# 18650_pack_v1.net
KiCad netlist of a schematic drawn in EAGLE
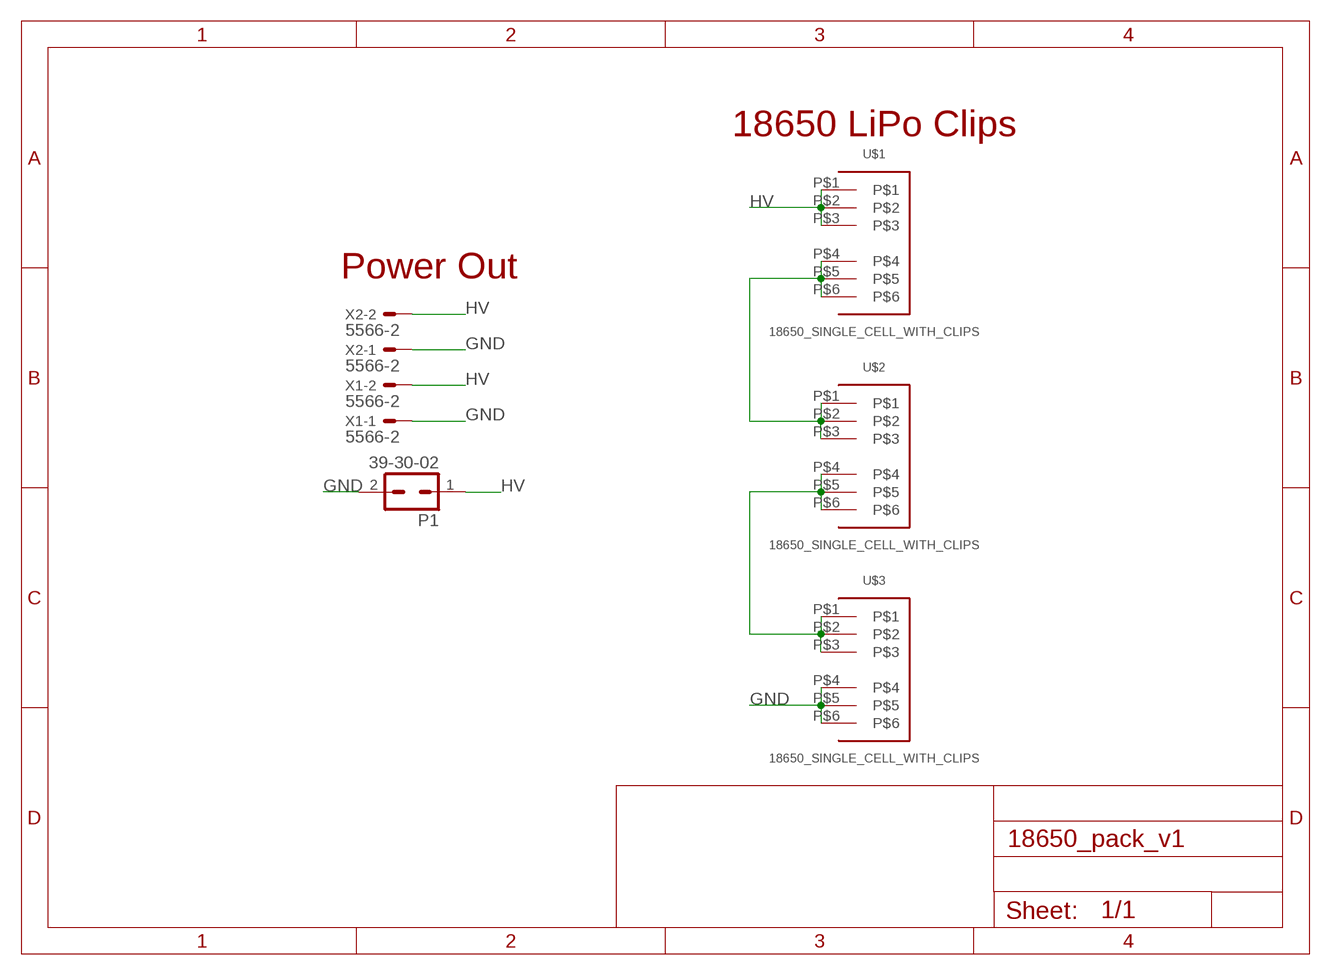
[diagram p0: schematic, sheet 1]

(export (version "E")
  (design (tool "Eeschema 10.0.6"))
  (components
    (comp (ref "P1")
      (value "39-30-02")
      (footprint "eagle-import:39-30-_02_")
      (libsource (lib "eagle-import") (part "39-30-?02?"))
    )
    (comp (ref "U$1")
      (value "18650_SINGLE_CELL_WITH_CLIPS")
      (footprint "eagle-import:3PINBATTERY_CLIP_1_CELL_18650")
      (libsource (lib "eagle-import") (part "18650_SINGLE_CELL_WITH_CLIPS"))
    )
    (comp (ref "U$2")
      (value "18650_SINGLE_CELL_WITH_CLIPS")
      (footprint "eagle-import:3PINBATTERY_CLIP_1_CELL_18650")
      (libsource (lib "eagle-import") (part "18650_SINGLE_CELL_WITH_CLIPS"))
    )
    (comp (ref "U$3")
      (value "18650_SINGLE_CELL_WITH_CLIPS")
      (footprint "eagle-import:3PINBATTERY_CLIP_1_CELL_18650")
      (libsource (lib "eagle-import") (part "18650_SINGLE_CELL_WITH_CLIPS"))
    )
    (comp (ref "X1")
      (value "5566-2")
      (footprint "eagle-import:5566-2")
      (fields (field (name "MF") "MOLEX"))
      (libsource (lib "eagle-import") (part "5566-2"))
    )
    (comp (ref "X2")
      (value "5566-2")
      (footprint "eagle-import:5566-2")
      (fields (field (name "MF") "MOLEX"))
      (libsource (lib "eagle-import") (part "5566-2"))
    )
  )
  (nets
    (net (code "1") (name "/GND") (class "Default")
      (node (ref "P1") (pin "2") (pinfunction "2_2") (pintype "passive"))
      (node (ref "U$3") (pin "P$4") (pinfunction "P$4_P$4") (pintype "bidirectional"))
      (node (ref "U$3") (pin "P$5") (pinfunction "P$5_P$5") (pintype "bidirectional"))
      (node (ref "U$3") (pin "P$6") (pinfunction "P$6_P$6") (pintype "bidirectional"))
      (node (ref "X1") (pin "1") (pinfunction "S_1") (pintype "passive"))
      (node (ref "X2") (pin "1") (pinfunction "S_1") (pintype "passive"))
    )
    (net (code "2") (name "/HV") (class "Default")
      (node (ref "P1") (pin "1") (pinfunction "1_1") (pintype "passive"))
      (node (ref "U$1") (pin "P$1") (pinfunction "P$1_P$1") (pintype "bidirectional"))
      (node (ref "U$1") (pin "P$2") (pinfunction "P$2_P$2") (pintype "bidirectional"))
      (node (ref "U$1") (pin "P$3") (pinfunction "P$3_P$3") (pintype "bidirectional"))
      (node (ref "X1") (pin "2") (pinfunction "S_2") (pintype "passive"))
      (node (ref "X2") (pin "2") (pinfunction "S_2") (pintype "passive"))
    )
    (net (code "3") (name "Net-(U$1-PadP$4)") (class "Default")
      (node (ref "U$1") (pin "P$4") (pinfunction "P$4_P$4") (pintype "bidirectional"))
      (node (ref "U$1") (pin "P$5") (pinfunction "P$5_P$5") (pintype "bidirectional"))
      (node (ref "U$1") (pin "P$6") (pinfunction "P$6_P$6") (pintype "bidirectional"))
      (node (ref "U$2") (pin "P$1") (pinfunction "P$1_P$1") (pintype "bidirectional"))
      (node (ref "U$2") (pin "P$2") (pinfunction "P$2_P$2") (pintype "bidirectional"))
      (node (ref "U$2") (pin "P$3") (pinfunction "P$3_P$3") (pintype "bidirectional"))
    )
    (net (code "4") (name "Net-(U$2-PadP$4)") (class "Default")
      (node (ref "U$2") (pin "P$4") (pinfunction "P$4_P$4") (pintype "bidirectional"))
      (node (ref "U$2") (pin "P$5") (pinfunction "P$5_P$5") (pintype "bidirectional"))
      (node (ref "U$2") (pin "P$6") (pinfunction "P$6_P$6") (pintype "bidirectional"))
      (node (ref "U$3") (pin "P$1") (pinfunction "P$1_P$1") (pintype "bidirectional"))
      (node (ref "U$3") (pin "P$2") (pinfunction "P$2_P$2") (pintype "bidirectional"))
      (node (ref "U$3") (pin "P$3") (pinfunction "P$3_P$3") (pintype "bidirectional"))
    )
  )
)
